# sensor-weather-perfboard.net
KiCad netlist of a schematic drawn in EAGLE
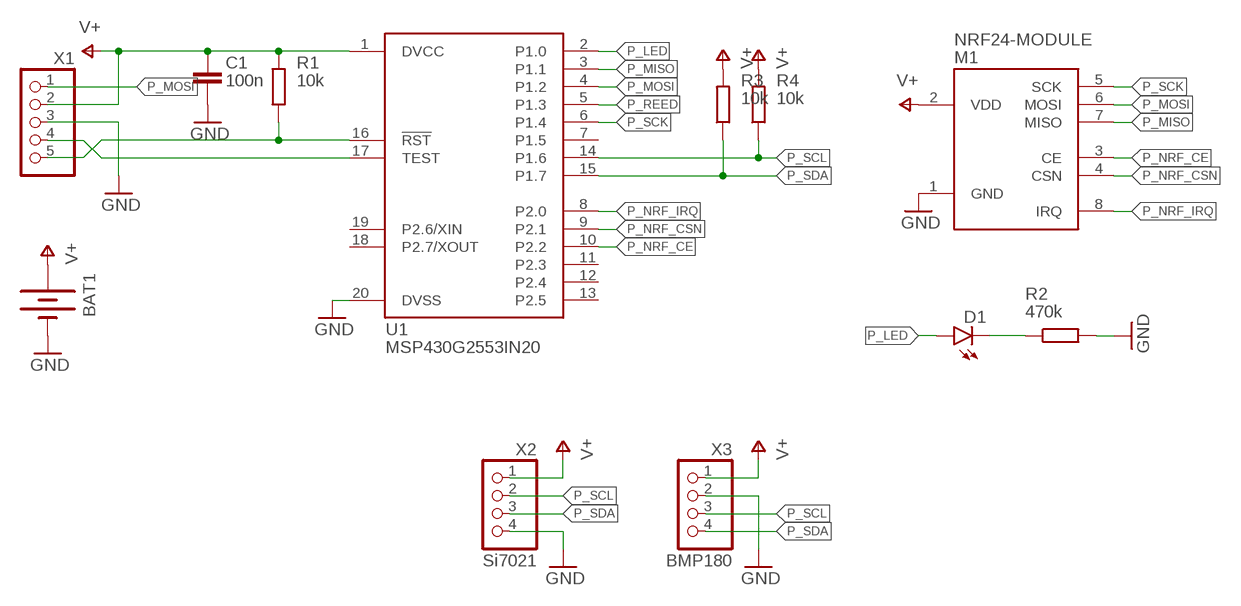
[diagram p0: schematic, sheet 1]

(export (version "E")
  (design (tool "Eeschema 10.0.6"))
  (components
    (comp (ref "BAT1")
      (value "BATTERY20PTH")
      (footprint "eagle-import:BATTCOM_20MM_PTH")
      (libsource (lib "eagle-import") (part "BATTERY20PTH"))
    )
    (comp (ref "C1")
      (value "100n")
      (footprint "eagle-import:C0603")
      (libsource (lib "eagle-import") (part "C0603"))
    )
    (comp (ref "D1")
      (value "LED5MM")
      (footprint "eagle-import:LED5MM")
      (libsource (lib "eagle-import") (part "LED5MM"))
    )
    (comp (ref "M1")
      (value "NRF24-MODULE")
      (footprint "eagle-import:NRF24-MODULE")
      (libsource (lib "eagle-import") (part "NRF24-MODULE"))
    )
    (comp (ref "R1")
      (value "10k")
      (footprint "eagle-import:R0603")
      (libsource (lib "eagle-import") (part "R0603"))
    )
    (comp (ref "R2")
      (value "470k")
      (footprint "eagle-import:R0603")
      (libsource (lib "eagle-import") (part "R0603"))
    )
    (comp (ref "R3")
      (value "10k")
      (footprint "eagle-import:R0603")
      (libsource (lib "eagle-import") (part "R0603"))
    )
    (comp (ref "R4")
      (value "10k")
      (footprint "eagle-import:R0603")
      (libsource (lib "eagle-import") (part "R0603"))
    )
    (comp (ref "U1")
      (value "MSP430G2553IN20")
      (footprint "eagle-import:DIL20")
      (libsource (lib "eagle-import") (part "MSP430G2553IN20"))
    )
    (comp (ref "X1")
      (value "PINHD_5_RND")
      (footprint "eagle-import:1X05")
      (libsource (lib "eagle-import") (part "PINHD_5_RND"))
    )
    (comp (ref "X2")
      (value "Si7021")
      (footprint "eagle-import:1X04")
      (libsource (lib "eagle-import") (part "PINHD_4_RND"))
    )
    (comp (ref "X3")
      (value "BMP180")
      (footprint "eagle-import:1X04")
      (libsource (lib "eagle-import") (part "PINHD_4_RND"))
    )
  )
  (nets
    (net (code "1") (name "GND") (class "Default")
      (node (ref "BAT1") (pin "2") (pinfunction "-_2") (pintype "power_in"))
      (node (ref "C1") (pin "2") (pinfunction "2_2") (pintype "passive"))
      (node (ref "M1") (pin "1") (pinfunction "GND_1") (pintype "bidirectional"))
      (node (ref "R2") (pin "2") (pinfunction "2_2") (pintype "passive"))
      (node (ref "U1") (pin "20") (pinfunction "DVSS_20") (pintype "bidirectional"))
      (node (ref "X1") (pin "3") (pinfunction "3_3") (pintype "passive"))
      (node (ref "X2") (pin "4") (pinfunction "4_4") (pintype "passive"))
      (node (ref "X3") (pin "2") (pinfunction "2_2") (pintype "passive"))
    )
    (net (code "2") (name "Net-(D1-C)") (class "Default")
      (node (ref "D1") (pin "K") (pinfunction "C_K") (pintype "passive"))
      (node (ref "R2") (pin "1") (pinfunction "1_1") (pintype "passive"))
    )
    (net (code "3") (name "Net-(U1-TEST)") (class "Default")
      (node (ref "U1") (pin "17") (pinfunction "TEST_17") (pintype "bidirectional"))
      (node (ref "X1") (pin "4") (pinfunction "4_4") (pintype "passive"))
    )
    (net (code "4") (name "Net-(U1-~{RST})") (class "Default")
      (node (ref "R1") (pin "1") (pinfunction "1_1") (pintype "passive"))
      (node (ref "U1") (pin "16") (pinfunction "~{RST}_16") (pintype "bidirectional"))
      (node (ref "X1") (pin "5") (pinfunction "5_5") (pintype "passive"))
    )
    (net (code "5") (name "P_LED") (class "Default")
      (node (ref "D1") (pin "A") (pinfunction "A_A") (pintype "passive"))
      (node (ref "U1") (pin "2") (pinfunction "P1.0_2") (pintype "bidirectional"))
    )
    (net (code "6") (name "P_MISO") (class "Default")
      (node (ref "M1") (pin "7") (pinfunction "MISO_7") (pintype "bidirectional"))
      (node (ref "U1") (pin "3") (pinfunction "P1.1_3") (pintype "bidirectional"))
    )
    (net (code "7") (name "P_MOSI") (class "Default")
      (node (ref "M1") (pin "6") (pinfunction "MOSI_6") (pintype "bidirectional"))
      (node (ref "U1") (pin "4") (pinfunction "P1.2_4") (pintype "bidirectional"))
      (node (ref "X1") (pin "1") (pinfunction "1_1") (pintype "passive"))
    )
    (net (code "8") (name "P_NRF_CE") (class "Default")
      (node (ref "M1") (pin "3") (pinfunction "CE_3") (pintype "bidirectional"))
      (node (ref "U1") (pin "10") (pinfunction "P2.2_10") (pintype "bidirectional"))
    )
    (net (code "9") (name "P_NRF_CSN") (class "Default")
      (node (ref "M1") (pin "4") (pinfunction "CSN_4") (pintype "bidirectional"))
      (node (ref "U1") (pin "9") (pinfunction "P2.1_9") (pintype "bidirectional"))
    )
    (net (code "10") (name "P_NRF_IRQ") (class "Default")
      (node (ref "M1") (pin "8") (pinfunction "IRQ_8") (pintype "bidirectional"))
      (node (ref "U1") (pin "8") (pinfunction "P2.0_8") (pintype "bidirectional"))
    )
    (net (code "11") (name "P_REED") (class "Default")
      (node (ref "U1") (pin "5") (pinfunction "P1.3_5") (pintype "bidirectional"))
    )
    (net (code "12") (name "P_SCK") (class "Default")
      (node (ref "M1") (pin "5") (pinfunction "SCK_5") (pintype "bidirectional"))
      (node (ref "U1") (pin "6") (pinfunction "P1.4_6") (pintype "bidirectional"))
    )
    (net (code "13") (name "P_SCL") (class "Default")
      (node (ref "R4") (pin "1") (pinfunction "1_1") (pintype "passive"))
      (node (ref "U1") (pin "14") (pinfunction "P1.6_14") (pintype "bidirectional"))
      (node (ref "X2") (pin "2") (pinfunction "2_2") (pintype "passive"))
      (node (ref "X3") (pin "3") (pinfunction "3_3") (pintype "passive"))
    )
    (net (code "14") (name "P_SDA") (class "Default")
      (node (ref "R3") (pin "1") (pinfunction "1_1") (pintype "passive"))
      (node (ref "U1") (pin "15") (pinfunction "P1.7_15") (pintype "bidirectional"))
      (node (ref "X2") (pin "3") (pinfunction "3_3") (pintype "passive"))
      (node (ref "X3") (pin "4") (pinfunction "4_4") (pintype "passive"))
    )
    (net (code "15") (name "V+") (class "Default")
      (node (ref "BAT1") (pin "1") (pinfunction "+_1") (pintype "power_in"))
      (node (ref "C1") (pin "1") (pinfunction "1_1") (pintype "passive"))
      (node (ref "M1") (pin "2") (pinfunction "VDD_2") (pintype "bidirectional"))
      (node (ref "R1") (pin "2") (pinfunction "2_2") (pintype "passive"))
      (node (ref "R3") (pin "2") (pinfunction "2_2") (pintype "passive"))
      (node (ref "R4") (pin "2") (pinfunction "2_2") (pintype "passive"))
      (node (ref "U1") (pin "1") (pinfunction "DVCC_1") (pintype "bidirectional"))
      (node (ref "X1") (pin "2") (pinfunction "2_2") (pintype "passive"))
      (node (ref "X2") (pin "1") (pinfunction "1_1") (pintype "passive"))
      (node (ref "X3") (pin "1") (pinfunction "1_1") (pintype "passive"))
    )
    (net (code "16") (name "unconnected-(U1-P1.5-Pad7)") (class "Default")
      (node (ref "U1") (pin "7") (pinfunction "P1.5_7") (pintype "bidirectional"))
    )
    (net (code "17") (name "unconnected-(U1-P2.3-Pad11)") (class "Default")
      (node (ref "U1") (pin "11") (pinfunction "P2.3_11") (pintype "bidirectional"))
    )
    (net (code "18") (name "unconnected-(U1-P2.4-Pad12)") (class "Default")
      (node (ref "U1") (pin "12") (pinfunction "P2.4_12") (pintype "bidirectional"))
    )
    (net (code "19") (name "unconnected-(U1-P2.5-Pad13)") (class "Default")
      (node (ref "U1") (pin "13") (pinfunction "P2.5_13") (pintype "bidirectional"))
    )
    (net (code "20") (name "unconnected-(U1-P2.6{slash}XIN-Pad19)") (class "Default")
      (node (ref "U1") (pin "19") (pinfunction "P2.6/XIN_19") (pintype "bidirectional"))
    )
    (net (code "21") (name "unconnected-(U1-P2.7{slash}XOUT-Pad18)") (class "Default")
      (node (ref "U1") (pin "18") (pinfunction "P2.7/XOUT_18") (pintype "bidirectional"))
    )
  )
)
